# Motor-Z.net
KiCad netlist of a schematic drawn in Altium Designer
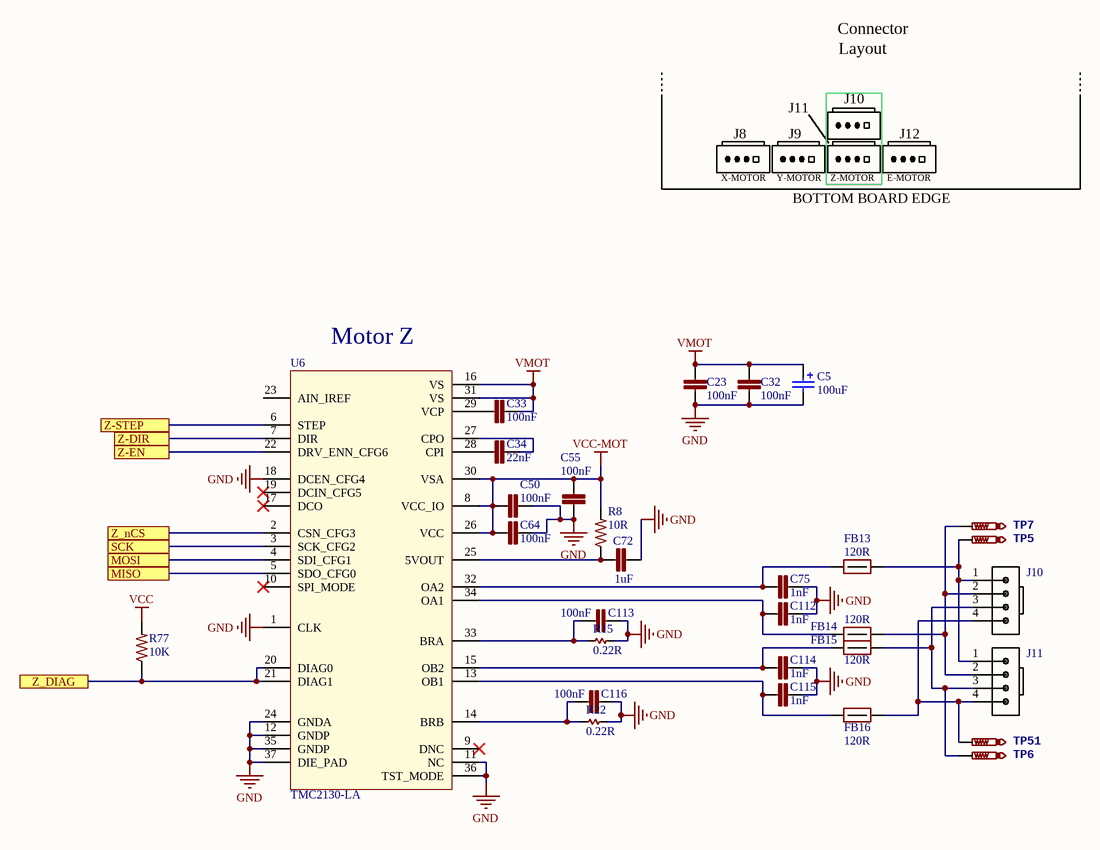
[diagram p0: Motor-Z.SchDoc]

(export (version "E")
  (design (tool "Eeschema 10.0.6"))
  (components
    (comp (ref "C5")
      (value "100uF")
      (footprint "CAP-ELEC-063063077")
      (description "CAP ALUM 100UF 35V 20% SMD")
      (fields (field (name "MANUFACTURER") "Nichicon") (field (name "TOLERANCE") "+/- 20%"))
      (libsource (lib "3Delight") (part "UWT1V101MCL1GS"))
    )
    (comp (ref "C23")
      (value "100nF")
      (footprint "C0603")
      (description "CAP CER 0603 100nF 50V 10% X7R")
      (fields (field (name "MANUFACTURER") "Kemet") (field (name "TOLERANCE") "+/- 10%"))
      (libsource (lib "3Delight") (part "C0603C104K5RACTU"))
    )
    (comp (ref "C32")
      (value "100nF")
      (footprint "C0603")
      (description "CAP CER 0603 100nF 50V 10% X7R")
      (fields (field (name "MANUFACTURER") "Kemet") (field (name "TOLERANCE") "+/- 10%"))
      (libsource (lib "3Delight") (part "C0603C104K5RACTU"))
    )
    (comp (ref "C33")
      (value "100nF")
      (footprint "C0603")
      (description "CAP CER 0603 100nF 50V 10% X7R")
      (fields (field (name "MANUFACTURER") "Kemet") (field (name "TOLERANCE") "+/- 10%"))
      (libsource (lib "") (part "C0603C104K5RACTU_2"))
    )
    (comp (ref "C34")
      (value "22nF")
      (footprint "C0402")
      (description "CAP CER 0402 22nF ±10% 50V X7R")
      (fields (field (name "MANUFACTURER") "YAGEO") (field (name "TOLERANCE") "+/- 10%"))
      (libsource (lib "3Delight") (part "GCM155R71H223KA55D"))
    )
    (comp (ref "C50")
      (value "100nF")
      (footprint "C0402")
      (description "CAP CER 0402 100nF 16V 10% X7R")
      (fields (field (name "MANUFACTURER") "Murata") (field (name "TOLERANCE") "+/- 10%"))
      (libsource (lib "3Delight") (part "GRM155R71C104KA88D"))
    )
    (comp (ref "C55")
      (value "100nF")
      (footprint "C0402")
      (description "CAP CER 0402 100nF 16V 10% X7R")
      (fields (field (name "MANUFACTURER") "Murata") (field (name "TOLERANCE") "+/- 10%"))
      (libsource (lib "") (part "GRM155R71C104KA88D_1"))
    )
    (comp (ref "C64")
      (value "100nF")
      (footprint "C0402")
      (description "CAP CER 0402 100nF 16V 10% X7R")
      (fields (field (name "MANUFACTURER") "Murata") (field (name "TOLERANCE") "+/- 10%"))
      (libsource (lib "3Delight") (part "GRM155R71C104KA88D"))
    )
    (comp (ref "C72")
      (value "1uF")
      (footprint "C0402")
      (description "CAP CER 0402 1uF 6.3V 10% X5R")
      (fields (field (name "MANUFACTURER") "Murata") (field (name "TOLERANCE") "+/- 10%"))
      (libsource (lib "3Delight") (part "GRM155R60J105KE19D"))
    )
    (comp (ref "C75")
      (value "1nF")
      (footprint "C0603")
      (description "CAP CER 0603  1nF 50v 10% X7R")
      (fields (field (name "MANUFACTURER") "Kemet") (field (name "TOLERANCE") "+/- 10%"))
      (libsource (lib "3Delight") (part "C0603C102K5RACTU"))
    )
    (comp (ref "C112")
      (value "1nF")
      (footprint "C0603")
      (description "CAP CER 0603  1nF 50v 10% X7R")
      (fields (field (name "MANUFACTURER") "Kemet") (field (name "TOLERANCE") "+/- 10%"))
      (libsource (lib "3Delight") (part "C0603C102K5RACTU"))
    )
    (comp (ref "C113")
      (value "100nF")
      (footprint "C0603")
      (description "CAP CER 0603 100nF 50V 10% X7R")
      (fields (field (name "MANUFACTURER") "Kemet") (field (name "TOLERANCE") "+/- 10%"))
      (libsource (lib "") (part "C0603C104K5RACTU_1"))
    )
    (comp (ref "C114")
      (value "1nF")
      (footprint "C0603")
      (description "CAP CER 0603  1nF 50v 10% X7R")
      (fields (field (name "MANUFACTURER") "Kemet") (field (name "TOLERANCE") "+/- 10%"))
      (libsource (lib "3Delight") (part "C0603C102K5RACTU"))
    )
    (comp (ref "C115")
      (value "1nF")
      (footprint "C0603")
      (description "CAP CER 0603  1nF 50v 10% X7R")
      (fields (field (name "MANUFACTURER") "Kemet") (field (name "TOLERANCE") "+/- 10%"))
      (libsource (lib "3Delight") (part "C0603C102K5RACTU"))
    )
    (comp (ref "C116")
      (value "100nF")
      (footprint "C0603")
      (description "CAP CER 0603 100nF 50V 10% X7R")
      (fields (field (name "MANUFACTURER") "Kemet") (field (name "TOLERANCE") "+/- 10%"))
      (libsource (lib "") (part "C0603C104K5RACTU_1"))
    )
    (comp (ref "FB13")
      (value "120R")
      (footprint "FB0603")
      (description "FERRITE BEAD 120 OHM 0603 1LN")
      (fields (field (name "MANUFACTURER") "Samsung") (field (name "PART") "FERRITE 120R 3A 0603"))
      (libsource (lib "Inductors") (part "FERRITE 120R 3A 0603"))
    )
    (comp (ref "FB14")
      (value "120R")
      (footprint "FB0603")
      (description "FERRITE BEAD 120 OHM 0603 1LN")
      (fields (field (name "MANUFACTURER") "Samsung") (field (name "PART") "FERRITE 120R 3A 0603"))
      (libsource (lib "Inductors") (part "FERRITE 120R 3A 0603"))
    )
    (comp (ref "FB15")
      (value "120R")
      (footprint "FB0603")
      (description "FERRITE BEAD 120 OHM 0603 1LN")
      (fields (field (name "MANUFACTURER") "Samsung") (field (name "PART") "FERRITE 120R 3A 0603"))
      (libsource (lib "Inductors") (part "FERRITE 120R 3A 0603"))
    )
    (comp (ref "FB16")
      (value "120R")
      (footprint "FB0603")
      (description "FERRITE BEAD 120 OHM 0603 1LN")
      (fields (field (name "MANUFACTURER") "Samsung") (field (name "PART") "FERRITE 120R 3A 0603"))
      (libsource (lib "Inductors") (part "FERRITE 120R 3A 0603"))
    )
    (comp (ref "J10")
      (value "Molex 0705430003")
      (footprint "4POL254 PIN-IN-PASTE")
      (description "Molex 4 Pin Clip Connector")
      (libsource (lib "Connectors") (part "Molex 0705430003 PIN-IN-PASTE"))
    )
    (comp (ref "J11")
      (value "Molex 0705430003")
      (footprint "4POL254 PIN-IN-PASTE")
      (description "Molex 4 Pin Clip Connector")
      (libsource (lib "Connectors") (part "Molex 0705430003 PIN-IN-PASTE"))
    )
    (comp (ref "R8")
      (value "10R")
      (footprint "R0402")
      (description "RES SMD 10 OHM 1% 1/16W 0402")
      (fields (field (name "MANUFACTURER") "Yageo") (field (name "TOLERANCE") "+/- 1%"))
      (libsource (lib "3Delight") (part "RC0402FR-0710RL"))
    )
    (comp (ref "R15")
      (value "0.22R")
      (footprint "R1206")
      (description "RES SMD 0.22 OHM 1% 1/3W 1206")
      (fields (field (name "MANUFACTURER") "Panasonic") (field (name "TOLERANCE") "+/- 1%"))
      (libsource (lib "Resistors") (part "0.22R 1% 1206"))
    )
    (comp (ref "R22")
      (value "0.22R")
      (footprint "R1206")
      (description "RES SMD 0.22 OHM 1% 1/3W 1206")
      (fields (field (name "MANUFACTURER") "Panasonic") (field (name "TOLERANCE") "+/- 1%"))
      (libsource (lib "Resistors") (part "0.22R 1% 1206"))
    )
    (comp (ref "R77")
      (value "10K")
      (footprint "R0402")
      (description "RES SMD 10K OHM 1% 1/16W 0402")
      (fields (field (name "MANUFACTURER") "Yageo") (field (name "PART") "10k 1% 0402"))
      (libsource (lib "3Delight") (part "RC0402FR-0710KP"))
    )
    (comp (ref "TP5")
      (value "TestPoint")
      (footprint "TP1-27")
      (description "Test Point")
      (libsource (lib "3Delight") (part "TestPoint"))
    )
    (comp (ref "TP6")
      (value "TestPoint")
      (footprint "TP1-27")
      (description "Test Point")
      (libsource (lib "3Delight") (part "TestPoint"))
    )
    (comp (ref "TP7")
      (value "TestPoint")
      (footprint "TP1-27")
      (description "Test Point")
      (libsource (lib "3Delight") (part "TestPoint"))
    )
    (comp (ref "TP51")
      (value "TestPoint")
      (footprint "TP1-27")
      (description "Test Point")
      (libsource (lib "3Delight") (part "TestPoint"))
    )
    (comp (ref "U6")
      (value "TMC2130-LA")
      (footprint "QFN36-DualSolderMask")
      (description "IC STEPPER MOTOR DVR SPI 36QFN")
      (fields (field (name "MANUFACTURER") "Trinamic") (field (name "PART") "TMC2130"))
      (libsource (lib "ICs-Motor Controller") (part "TMC2130-DualSolderMask"))
    )
  )
  (nets
    (net (code "1") (name "/MISO") (class "Default")
      (node (ref "U6") (pin "5") (pinfunction "SDO_CFG0_5") (pintype "passive"))
    )
    (net (code "2") (name "/MOSI") (class "Default")
      (node (ref "U6") (pin "4") (pinfunction "SDI_CFG1_4") (pintype "passive"))
    )
    (net (code "3") (name "/SCK") (class "Default")
      (node (ref "U6") (pin "3") (pinfunction "SCK_CFG2_3") (pintype "passive"))
    )
    (net (code "4") (name "/Z-DIR") (class "Default")
      (node (ref "U6") (pin "7") (pinfunction "DIR_7") (pintype "passive"))
    )
    (net (code "5") (name "/Z-EN") (class "Default")
      (node (ref "U6") (pin "22") (pinfunction "DRV_ENN_CFG6_22") (pintype "passive"))
    )
    (net (code "6") (name "/Z-STEP") (class "Default")
      (node (ref "U6") (pin "6") (pinfunction "STEP_6") (pintype "passive"))
    )
    (net (code "7") (name "/Z_DIAG") (class "Default")
      (node (ref "R77") (pin "1") (pinfunction "1_1") (pintype "passive"))
      (node (ref "U6") (pin "20") (pinfunction "DIAG0_20") (pintype "passive"))
      (node (ref "U6") (pin "21") (pinfunction "DIAG1_21") (pintype "passive"))
    )
    (net (code "8") (name "/Z_nCS") (class "Default")
      (node (ref "U6") (pin "2") (pinfunction "CSN_CFG3_2") (pintype "passive"))
    )
    (net (code "9") (name "GND") (class "Default")
      (node (ref "C112") (pin "2") (pinfunction "2_2") (pintype "passive"))
      (node (ref "C113") (pin "1") (pinfunction "1_1") (pintype "passive"))
      (node (ref "C114") (pin "2") (pinfunction "2_2") (pintype "passive"))
      (node (ref "C115") (pin "2") (pinfunction "2_2") (pintype "passive"))
      (node (ref "C116") (pin "1") (pinfunction "1_1") (pintype "passive"))
      (node (ref "C23") (pin "1") (pinfunction "1_1") (pintype "passive"))
      (node (ref "C32") (pin "1") (pinfunction "1_1") (pintype "passive"))
      (node (ref "C5") (pin "2") (pinfunction "2_2") (pintype "passive"))
      (node (ref "C50") (pin "1") (pinfunction "1_1") (pintype "passive"))
      (node (ref "C55") (pin "1") (pinfunction "1_1") (pintype "passive"))
      (node (ref "C64") (pin "1") (pinfunction "1_1") (pintype "passive"))
      (node (ref "C72") (pin "2") (pinfunction "2_2") (pintype "passive"))
      (node (ref "C75") (pin "2") (pinfunction "2_2") (pintype "passive"))
      (node (ref "R15") (pin "2") (pinfunction "2_2") (pintype "passive"))
      (node (ref "R22") (pin "2") (pinfunction "2_2") (pintype "passive"))
      (node (ref "U6") (pin "1") (pinfunction "CLK_1") (pintype "passive"))
      (node (ref "U6") (pin "11") (pinfunction "NC_11") (pintype "passive"))
      (node (ref "U6") (pin "12") (pinfunction "GNDP_12") (pintype "passive"))
      (node (ref "U6") (pin "18") (pinfunction "DCEN_CFG4_18") (pintype "passive"))
      (node (ref "U6") (pin "24") (pinfunction "GNDA_24") (pintype "passive"))
      (node (ref "U6") (pin "35") (pinfunction "GNDP_35") (pintype "passive"))
      (node (ref "U6") (pin "36") (pinfunction "TST_MODE_36") (pintype "passive"))
      (node (ref "U6") (pin "37") (pinfunction "DIE_PAD_37") (pintype "passive"))
    )
    (net (code "10") (name "Net-(FB13-Pad2)") (class "Default")
      (node (ref "FB13") (pin "2") (pinfunction "2_2") (pintype "passive"))
      (node (ref "J10") (pin "1") (pinfunction "1_1") (pintype "passive"))
      (node (ref "J11") (pin "1") (pinfunction "1_1") (pintype "passive"))
      (node (ref "TP5") (pin "TP") (pinfunction "TP_TP") (pintype "passive"))
    )
    (net (code "11") (name "Net-(FB14-Pad2)") (class "Default")
      (node (ref "FB14") (pin "2") (pinfunction "2_2") (pintype "passive"))
      (node (ref "J10") (pin "2") (pinfunction "2_2") (pintype "passive"))
      (node (ref "J11") (pin "2") (pinfunction "2_2") (pintype "passive"))
      (node (ref "TP7") (pin "TP") (pinfunction "TP_TP") (pintype "passive"))
    )
    (net (code "12") (name "Net-(FB15-Pad2)") (class "Default")
      (node (ref "FB15") (pin "2") (pinfunction "2_2") (pintype "passive"))
      (node (ref "J10") (pin "3") (pinfunction "3_3") (pintype "passive"))
      (node (ref "J11") (pin "3") (pinfunction "3_3") (pintype "passive"))
      (node (ref "TP6") (pin "TP") (pinfunction "TP_TP") (pintype "passive"))
    )
    (net (code "13") (name "Net-(FB16-Pad2)") (class "Default")
      (node (ref "FB16") (pin "2") (pinfunction "2_2") (pintype "passive"))
      (node (ref "J10") (pin "4") (pinfunction "4_4") (pintype "passive"))
      (node (ref "J11") (pin "4") (pinfunction "4_4") (pintype "passive"))
      (node (ref "TP51") (pin "TP") (pinfunction "TP_TP") (pintype "passive"))
    )
    (net (code "14") (name "Net-(U6-5VOUT)") (class "Default")
      (node (ref "C72") (pin "1") (pinfunction "1_1") (pintype "passive"))
      (node (ref "R8") (pin "1") (pinfunction "1_1") (pintype "passive"))
      (node (ref "U6") (pin "25") (pinfunction "5VOUT_25") (pintype "passive"))
    )
    (net (code "15") (name "Net-(U6-BRA)") (class "Default")
      (node (ref "C113") (pin "2") (pinfunction "2_2") (pintype "passive"))
      (node (ref "R15") (pin "1") (pinfunction "1_1") (pintype "passive"))
      (node (ref "U6") (pin "33") (pinfunction "BRA_33") (pintype "passive"))
    )
    (net (code "16") (name "Net-(U6-BRB)") (class "Default")
      (node (ref "C116") (pin "2") (pinfunction "2_2") (pintype "passive"))
      (node (ref "R22") (pin "1") (pinfunction "1_1") (pintype "passive"))
      (node (ref "U6") (pin "14") (pinfunction "BRB_14") (pintype "passive"))
    )
    (net (code "17") (name "Net-(U6-CPI)") (class "Default")
      (node (ref "C34") (pin "1") (pinfunction "1_1") (pintype "passive"))
      (node (ref "U6") (pin "28") (pinfunction "CPI_28") (pintype "passive"))
    )
    (net (code "18") (name "Net-(U6-CPO)") (class "Default")
      (node (ref "C34") (pin "2") (pinfunction "2_2") (pintype "passive"))
      (node (ref "U6") (pin "27") (pinfunction "CPO_27") (pintype "passive"))
    )
    (net (code "19") (name "Net-(U6-OA1)") (class "Default")
      (node (ref "C112") (pin "1") (pinfunction "1_1") (pintype "passive"))
      (node (ref "FB14") (pin "1") (pinfunction "1_1") (pintype "passive"))
      (node (ref "U6") (pin "34") (pinfunction "OA1_34") (pintype "passive"))
    )
    (net (code "20") (name "Net-(U6-OA2)") (class "Default")
      (node (ref "C75") (pin "1") (pinfunction "1_1") (pintype "passive"))
      (node (ref "FB13") (pin "1") (pinfunction "1_1") (pintype "passive"))
      (node (ref "U6") (pin "32") (pinfunction "OA2_32") (pintype "passive"))
    )
    (net (code "21") (name "Net-(U6-OB1)") (class "Default")
      (node (ref "C115") (pin "1") (pinfunction "1_1") (pintype "passive"))
      (node (ref "FB16") (pin "1") (pinfunction "1_1") (pintype "passive"))
      (node (ref "U6") (pin "13") (pinfunction "OB1_13") (pintype "passive"))
    )
    (net (code "22") (name "Net-(U6-OB2)") (class "Default")
      (node (ref "C114") (pin "1") (pinfunction "1_1") (pintype "passive"))
      (node (ref "FB15") (pin "1") (pinfunction "1_1") (pintype "passive"))
      (node (ref "U6") (pin "15") (pinfunction "OB2_15") (pintype "passive"))
    )
    (net (code "23") (name "Net-(U6-VCP)") (class "Default")
      (node (ref "C33") (pin "1") (pinfunction "1_1") (pintype "passive"))
      (node (ref "U6") (pin "29") (pinfunction "VCP_29") (pintype "passive"))
    )
    (net (code "24") (name "VCC") (class "Default")
      (node (ref "R77") (pin "2") (pinfunction "2_2") (pintype "passive"))
    )
    (net (code "25") (name "VCC-MOT") (class "Default")
      (node (ref "C50") (pin "2") (pinfunction "2_2") (pintype "passive"))
      (node (ref "C55") (pin "2") (pinfunction "2_2") (pintype "passive"))
      (node (ref "C64") (pin "2") (pinfunction "2_2") (pintype "passive"))
      (node (ref "R8") (pin "2") (pinfunction "2_2") (pintype "passive"))
      (node (ref "U6") (pin "26") (pinfunction "VCC_26") (pintype "passive"))
      (node (ref "U6") (pin "30") (pinfunction "VSA_30") (pintype "passive"))
      (node (ref "U6") (pin "8") (pinfunction "VCC_IO_8") (pintype "passive"))
    )
    (net (code "26") (name "VMOT") (class "Default")
      (node (ref "C23") (pin "2") (pinfunction "2_2") (pintype "passive"))
      (node (ref "C32") (pin "2") (pinfunction "2_2") (pintype "passive"))
      (node (ref "C33") (pin "2") (pinfunction "2_2") (pintype "passive"))
      (node (ref "C5") (pin "1") (pinfunction "1_1") (pintype "passive"))
      (node (ref "U6") (pin "16") (pinfunction "VS_16") (pintype "passive"))
      (node (ref "U6") (pin "31") (pinfunction "VS_31") (pintype "passive"))
    )
    (net (code "27") (name "unconnected-(U6-AIN_IREF-Pad23)") (class "Default")
      (node (ref "U6") (pin "23") (pinfunction "AIN_IREF_23") (pintype "passive"))
    )
    (net (code "28") (name "unconnected-(U6-DCIN_CFG5-Pad19)") (class "Default")
      (node (ref "U6") (pin "19") (pinfunction "DCIN_CFG5_19") (pintype "passive+no_connect"))
    )
    (net (code "29") (name "unconnected-(U6-DCO-Pad17)") (class "Default")
      (node (ref "U6") (pin "17") (pinfunction "DCO_17") (pintype "passive+no_connect"))
    )
    (net (code "30") (name "unconnected-(U6-DNC-Pad9)") (class "Default")
      (node (ref "U6") (pin "9") (pinfunction "DNC_9") (pintype "passive+no_connect"))
    )
    (net (code "31") (name "unconnected-(U6-SPI_MODE-Pad10)") (class "Default")
      (node (ref "U6") (pin "10") (pinfunction "SPI_MODE_10") (pintype "passive+no_connect"))
    )
  )
)
